# RAM_64K.net
KiCad netlist of a schematic drawn in EAGLE
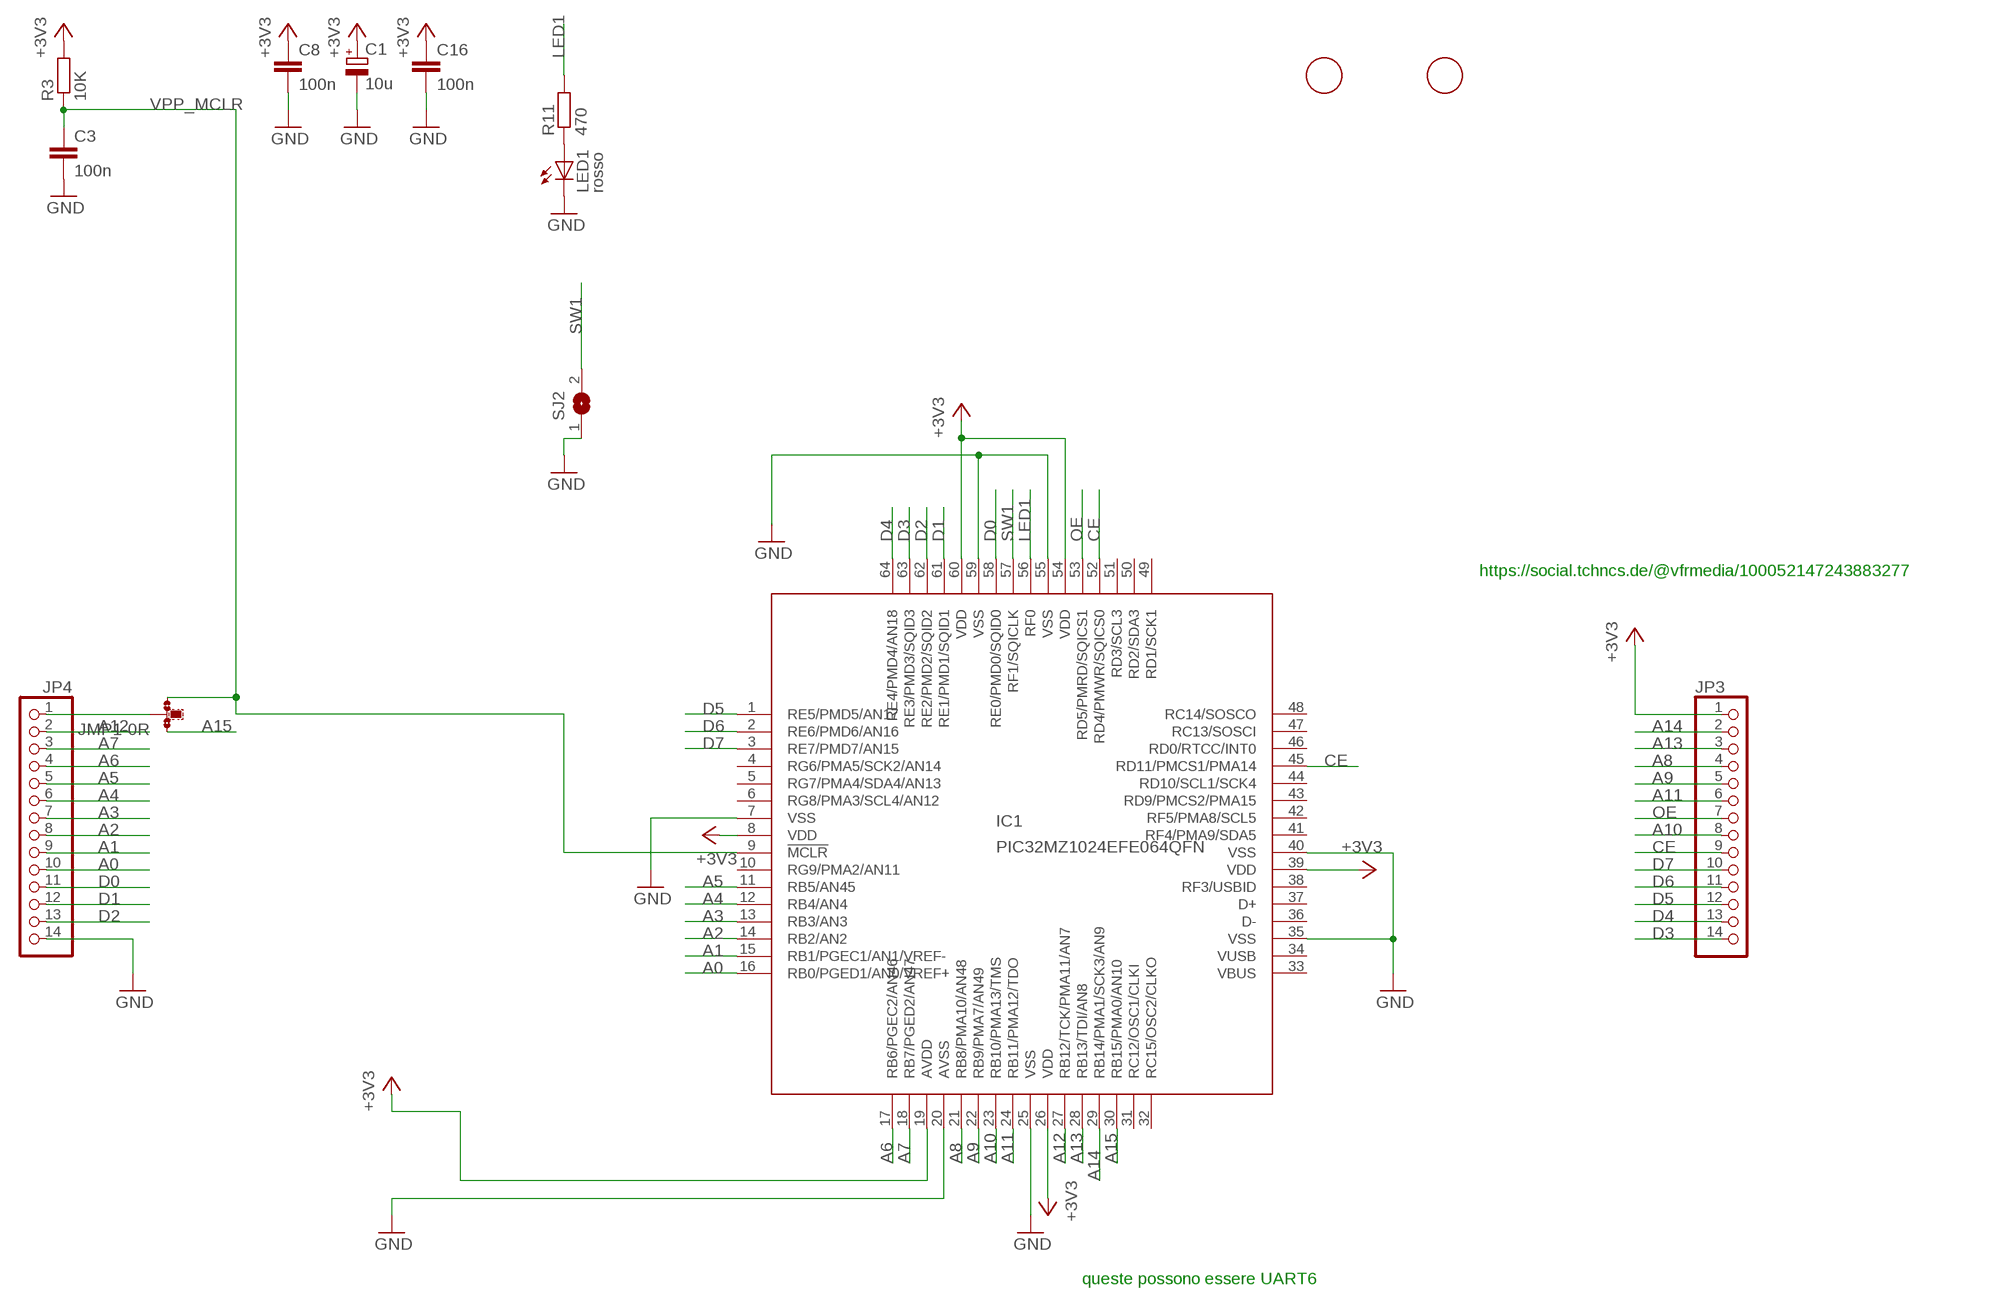
[diagram p0: schematic, sheet 1]

(export (version "E")
  (design (tool "Eeschema 10.0.6"))
  (components
    (comp (ref "C1")
      (value "10u")
      (footprint "eagle-import:SMC_B")
      (libsource (lib "eagle-import") (part "CPOL-EUSMCB"))
    )
    (comp (ref "C3")
      (value "100n")
      (footprint "eagle-import:C0805")
      (libsource (lib "eagle-import") (part "C-EUC0805"))
    )
    (comp (ref "C8")
      (value "100n")
      (footprint "eagle-import:C0805")
      (libsource (lib "eagle-import") (part "C-EUC0805"))
    )
    (comp (ref "C16")
      (value "100n")
      (footprint "eagle-import:C0805")
      (libsource (lib "eagle-import") (part "C-EUC0805"))
    )
    (comp (ref "F1")
      (value "FIDUCIAL")
      (footprint "eagle-import:FIDUCIAL_1MM")
      (libsource (lib "eagle-import") (part "FIDUCIAL"))
    )
    (comp (ref "F2")
      (value "FIDUCIAL")
      (footprint "eagle-import:FIDUCIAL_1MM")
      (libsource (lib "eagle-import") (part "FIDUCIAL"))
    )
    (comp (ref "IC1")
      (value "PIC32MZ1024EFE064QFN")
      (footprint "eagle-import:QFN64")
      (libsource (lib "eagle-import") (part "PIC32MZ1024EFE064QFN"))
    )
    (comp (ref "JMP1")
      (value "0R-JUMPC")
      (footprint "eagle-import:C0R-JMP")
      (libsource (lib "eagle-import") (part "0R-JUMPC"))
    )
    (comp (ref "JP3")
      (value "PINHD-1X14_2.54")
      (footprint "eagle-import:1X14")
      (libsource (lib "eagle-import") (part "PINHD-1X14_2.54"))
    )
    (comp (ref "JP4")
      (value "PINHD-1X14_2.54")
      (footprint "eagle-import:1X14")
      (libsource (lib "eagle-import") (part "PINHD-1X14_2.54"))
    )
    (comp (ref "LED1")
      (value "rosso")
      (footprint "eagle-import:CHIPLED_0805")
      (libsource (lib "eagle-import") (part "LEDCHIPLED_0805"))
    )
    (comp (ref "R3")
      (value "10K")
      (footprint "eagle-import:R0805")
      (libsource (lib "eagle-import") (part "R-EU_R0805"))
    )
    (comp (ref "R11")
      (value "470")
      (footprint "eagle-import:R0805")
      (libsource (lib "eagle-import") (part "R-EU_R0805"))
    )
    (comp (ref "SJ2") (value "SJ") (footprint "eagle-import:SJ") (libsource (lib "eagle-import") (part "SJ")))
  )
  (nets
    (net (code "1") (name "+3V3") (class "Default")
      (node (ref "C1") (pin "+") (pinfunction "+_+") (pintype "passive"))
      (node (ref "C16") (pin "1") (pinfunction "1_1") (pintype "passive"))
      (node (ref "C8") (pin "1") (pinfunction "1_1") (pintype "passive"))
      (node (ref "IC1") (pin "19") (pinfunction "AVDD_19") (pintype "power_in"))
      (node (ref "IC1") (pin "26") (pinfunction "VDD_26") (pintype "power_in"))
      (node (ref "IC1") (pin "39") (pinfunction "VDD_39") (pintype "power_in"))
      (node (ref "IC1") (pin "54") (pinfunction "VDD_54") (pintype "power_in"))
      (node (ref "IC1") (pin "60") (pinfunction "VDD_60") (pintype "power_in"))
      (node (ref "IC1") (pin "8") (pinfunction "VDD_8") (pintype "power_in"))
      (node (ref "JP3") (pin "1") (pinfunction "1_1") (pintype "passive"))
      (node (ref "R3") (pin "2") (pinfunction "2_2") (pintype "passive"))
    )
    (net (code "2") (name "/A0") (class "Default")
      (node (ref "IC1") (pin "16") (pinfunction "RB0/PGED1/AN0/VREF+_16") (pintype "bidirectional"))
      (node (ref "JP4") (pin "10") (pinfunction "10_10") (pintype "passive"))
    )
    (net (code "3") (name "/A1") (class "Default")
      (node (ref "IC1") (pin "15") (pinfunction "RB1/PGEC1/AN1/VREF-_15") (pintype "bidirectional"))
      (node (ref "JP4") (pin "9") (pinfunction "9_9") (pintype "passive"))
    )
    (net (code "4") (name "/A2") (class "Default")
      (node (ref "IC1") (pin "14") (pinfunction "RB2/AN2_14") (pintype "bidirectional"))
      (node (ref "JP4") (pin "8") (pinfunction "8_8") (pintype "passive"))
    )
    (net (code "5") (name "/A3") (class "Default")
      (node (ref "IC1") (pin "13") (pinfunction "RB3/AN3_13") (pintype "bidirectional"))
      (node (ref "JP4") (pin "7") (pinfunction "7_7") (pintype "passive"))
    )
    (net (code "6") (name "/A4") (class "Default")
      (node (ref "IC1") (pin "12") (pinfunction "RB4/AN4_12") (pintype "bidirectional"))
      (node (ref "JP4") (pin "6") (pinfunction "6_6") (pintype "passive"))
    )
    (net (code "7") (name "/A5") (class "Default")
      (node (ref "IC1") (pin "11") (pinfunction "RB5/AN45_11") (pintype "bidirectional"))
      (node (ref "JP4") (pin "5") (pinfunction "5_5") (pintype "passive"))
    )
    (net (code "8") (name "/A6") (class "Default")
      (node (ref "IC1") (pin "17") (pinfunction "RB6/PGEC2/AN46_17") (pintype "bidirectional"))
      (node (ref "JP4") (pin "4") (pinfunction "4_4") (pintype "passive"))
    )
    (net (code "9") (name "/A7") (class "Default")
      (node (ref "IC1") (pin "18") (pinfunction "RB7/PGED2/AN47_18") (pintype "bidirectional"))
      (node (ref "JP4") (pin "3") (pinfunction "3_3") (pintype "passive"))
    )
    (net (code "10") (name "/A8") (class "Default")
      (node (ref "IC1") (pin "21") (pinfunction "RB8/PMA10/AN48_21") (pintype "bidirectional"))
      (node (ref "JP3") (pin "4") (pinfunction "4_4") (pintype "passive"))
    )
    (net (code "11") (name "/A9") (class "Default")
      (node (ref "IC1") (pin "22") (pinfunction "RB9/PMA7/AN49_22") (pintype "bidirectional"))
      (node (ref "JP3") (pin "5") (pinfunction "5_5") (pintype "passive"))
    )
    (net (code "12") (name "/A10") (class "Default")
      (node (ref "IC1") (pin "23") (pinfunction "RB10/PMA13/TMS_23") (pintype "bidirectional"))
      (node (ref "JP3") (pin "8") (pinfunction "8_8") (pintype "passive"))
    )
    (net (code "13") (name "/A11") (class "Default")
      (node (ref "IC1") (pin "24") (pinfunction "RB11/PMA12/TDO_24") (pintype "bidirectional"))
      (node (ref "JP3") (pin "6") (pinfunction "6_6") (pintype "passive"))
    )
    (net (code "14") (name "/A12") (class "Default")
      (node (ref "IC1") (pin "27") (pinfunction "RB12/TCK/PMA11/AN7_27") (pintype "bidirectional"))
      (node (ref "JP4") (pin "2") (pinfunction "2_2") (pintype "passive"))
    )
    (net (code "15") (name "/A13") (class "Default")
      (node (ref "IC1") (pin "28") (pinfunction "RB13/TDI/AN8_28") (pintype "bidirectional"))
      (node (ref "JP3") (pin "3") (pinfunction "3_3") (pintype "passive"))
    )
    (net (code "16") (name "/A14") (class "Default")
      (node (ref "IC1") (pin "29") (pinfunction "RB14/PMA1/SCK3/AN9_29") (pintype "bidirectional"))
      (node (ref "JP3") (pin "2") (pinfunction "2_2") (pintype "passive"))
    )
    (net (code "17") (name "/A15") (class "Default")
      (node (ref "IC1") (pin "30") (pinfunction "RB15/PMA0/AN10_30") (pintype "bidirectional"))
      (node (ref "JMP1") (pin "1") (pinfunction "1_1") (pintype "passive"))
    )
    (net (code "18") (name "/CE") (class "Default")
      (node (ref "IC1") (pin "45") (pinfunction "RD11/PMCS1/PMA14_45") (pintype "bidirectional"))
      (node (ref "IC1") (pin "52") (pinfunction "RD4/PMWR/SQICS0_52") (pintype "bidirectional"))
      (node (ref "JP3") (pin "9") (pinfunction "9_9") (pintype "passive"))
    )
    (net (code "19") (name "/D0") (class "Default")
      (node (ref "IC1") (pin "58") (pinfunction "RE0/PMD0/SQID0_58") (pintype "bidirectional"))
      (node (ref "JP4") (pin "11") (pinfunction "11_11") (pintype "passive"))
    )
    (net (code "20") (name "/D1") (class "Default")
      (node (ref "IC1") (pin "61") (pinfunction "RE1/PMD1/SQID1_61") (pintype "bidirectional"))
      (node (ref "JP4") (pin "12") (pinfunction "12_12") (pintype "passive"))
    )
    (net (code "21") (name "/D2") (class "Default")
      (node (ref "IC1") (pin "62") (pinfunction "RE2/PMD2/SQID2_62") (pintype "bidirectional"))
      (node (ref "JP4") (pin "13") (pinfunction "13_13") (pintype "passive"))
    )
    (net (code "22") (name "/D3") (class "Default")
      (node (ref "IC1") (pin "63") (pinfunction "RE3/PMD3/SQID3_63") (pintype "bidirectional"))
      (node (ref "JP3") (pin "14") (pinfunction "14_14") (pintype "passive"))
    )
    (net (code "23") (name "/D4") (class "Default")
      (node (ref "IC1") (pin "64") (pinfunction "RE4/PMD4/AN18_64") (pintype "bidirectional"))
      (node (ref "JP3") (pin "13") (pinfunction "13_13") (pintype "passive"))
    )
    (net (code "24") (name "/D5") (class "Default")
      (node (ref "IC1") (pin "1") (pinfunction "RE5/PMD5/AN17_1") (pintype "bidirectional"))
      (node (ref "JP3") (pin "12") (pinfunction "12_12") (pintype "passive"))
    )
    (net (code "25") (name "/D6") (class "Default")
      (node (ref "IC1") (pin "2") (pinfunction "RE6/PMD6/AN16_2") (pintype "bidirectional"))
      (node (ref "JP3") (pin "11") (pinfunction "11_11") (pintype "passive"))
    )
    (net (code "26") (name "/D7") (class "Default")
      (node (ref "IC1") (pin "3") (pinfunction "RE7/PMD7/AN15_3") (pintype "bidirectional"))
      (node (ref "JP3") (pin "10") (pinfunction "10_10") (pintype "passive"))
    )
    (net (code "27") (name "/LED1") (class "Default")
      (node (ref "IC1") (pin "56") (pinfunction "RF0_56") (pintype "bidirectional"))
      (node (ref "R11") (pin "2") (pinfunction "2_2") (pintype "passive"))
    )
    (net (code "28") (name "/OE") (class "Default")
      (node (ref "IC1") (pin "53") (pinfunction "RD5/PMRD/SQICS1_53") (pintype "bidirectional"))
      (node (ref "JP3") (pin "7") (pinfunction "7_7") (pintype "passive"))
    )
    (net (code "29") (name "/SW1") (class "Default")
      (node (ref "IC1") (pin "57") (pinfunction "RF1/SQICLK_57") (pintype "bidirectional"))
      (node (ref "SJ2") (pin "2") (pinfunction "2_2") (pintype "passive"))
    )
    (net (code "30") (name "/VPP_MCLR") (class "Default")
      (node (ref "C3") (pin "1") (pinfunction "1_1") (pintype "passive"))
      (node (ref "IC1") (pin "9") (pinfunction "~{MCLR}_9") (pintype "input"))
      (node (ref "JMP1") (pin "3") (pinfunction "3_3") (pintype "passive"))
      (node (ref "R3") (pin "1") (pinfunction "1_1") (pintype "passive"))
    )
    (net (code "31") (name "/VUSB") (class "Default")
      (node (ref "IC1") (pin "34") (pinfunction "VUSB_34") (pintype "power_in"))
    )
    (net (code "32") (name "GND") (class "Default")
      (node (ref "C1") (pin "-") (pinfunction "-_-") (pintype "passive"))
      (node (ref "C16") (pin "2") (pinfunction "2_2") (pintype "passive"))
      (node (ref "C3") (pin "2") (pinfunction "2_2") (pintype "passive"))
      (node (ref "C8") (pin "2") (pinfunction "2_2") (pintype "passive"))
      (node (ref "IC1") (pin "20") (pinfunction "AVSS_20") (pintype "power_in"))
      (node (ref "IC1") (pin "25") (pinfunction "VSS_25") (pintype "power_in"))
      (node (ref "IC1") (pin "35") (pinfunction "VSS_35") (pintype "power_in"))
      (node (ref "IC1") (pin "40") (pinfunction "VSS_40") (pintype "power_in"))
      (node (ref "IC1") (pin "55") (pinfunction "VSS_55") (pintype "power_in"))
      (node (ref "IC1") (pin "59") (pinfunction "VSS_59") (pintype "power_in"))
      (node (ref "IC1") (pin "7") (pinfunction "VSS_7") (pintype "power_in"))
      (node (ref "JP4") (pin "14") (pinfunction "14_14") (pintype "passive"))
      (node (ref "LED1") (pin "C") (pinfunction "C_C") (pintype "passive"))
      (node (ref "SJ2") (pin "1") (pinfunction "1_1") (pintype "passive"))
    )
    (net (code "33") (name "Net-(JMP1-Pad2)") (class "Default")
      (node (ref "JMP1") (pin "2") (pinfunction "2_2") (pintype "passive"))
      (node (ref "JP4") (pin "1") (pinfunction "1_1") (pintype "passive"))
    )
    (net (code "34") (name "Net-(LED1-PadA)") (class "Default")
      (node (ref "LED1") (pin "A") (pinfunction "A_A") (pintype "passive"))
      (node (ref "R11") (pin "1") (pinfunction "1_1") (pintype "passive"))
    )
    (net (code "35") (name "unconnected-(IC1-D+-Pad37)") (class "Default")
      (node (ref "IC1") (pin "37") (pinfunction "D+_37") (pintype "passive"))
    )
    (net (code "36") (name "unconnected-(IC1-D--Pad36)") (class "Default")
      (node (ref "IC1") (pin "36") (pinfunction "D-_36") (pintype "passive"))
    )
    (net (code "37") (name "unconnected-(IC1-RC12{slash}OSC1{slash}CLKI-Pad31)") (class "Default")
      (node (ref "IC1") (pin "31") (pinfunction "RC12/OSC1/CLKI_31") (pintype "bidirectional"))
    )
    (net (code "38") (name "unconnected-(IC1-RC13{slash}SOSCI-Pad47)") (class "Default")
      (node (ref "IC1") (pin "47") (pinfunction "RC13/SOSCI_47") (pintype "bidirectional"))
    )
    (net (code "39") (name "unconnected-(IC1-RC14{slash}SOSCO-Pad48)") (class "Default")
      (node (ref "IC1") (pin "48") (pinfunction "RC14/SOSCO_48") (pintype "bidirectional"))
    )
    (net (code "40") (name "unconnected-(IC1-RC15{slash}OSC2{slash}CLKO-Pad32)") (class "Default")
      (node (ref "IC1") (pin "32") (pinfunction "RC15/OSC2/CLKO_32") (pintype "bidirectional"))
    )
    (net (code "41") (name "unconnected-(IC1-RD0{slash}RTCC{slash}INT0-Pad46)") (class "Default")
      (node (ref "IC1") (pin "46") (pinfunction "RD0/RTCC/INT0_46") (pintype "bidirectional"))
    )
    (net (code "42") (name "unconnected-(IC1-RD1{slash}SCK1-Pad49)") (class "Default")
      (node (ref "IC1") (pin "49") (pinfunction "RD1/SCK1_49") (pintype "bidirectional"))
    )
    (net (code "43") (name "unconnected-(IC1-RD2{slash}SDA3-Pad50)") (class "Default")
      (node (ref "IC1") (pin "50") (pinfunction "RD2/SDA3_50") (pintype "bidirectional"))
    )
    (net (code "44") (name "unconnected-(IC1-RD3{slash}SCL3-Pad51)") (class "Default")
      (node (ref "IC1") (pin "51") (pinfunction "RD3/SCL3_51") (pintype "bidirectional"))
    )
    (net (code "45") (name "unconnected-(IC1-RD9{slash}PMCS2{slash}PMA15-Pad43)") (class "Default")
      (node (ref "IC1") (pin "43") (pinfunction "RD9/PMCS2/PMA15_43") (pintype "bidirectional"))
    )
    (net (code "46") (name "unconnected-(IC1-RD10{slash}SCL1{slash}SCK4-Pad44)") (class "Default")
      (node (ref "IC1") (pin "44") (pinfunction "RD10/SCL1/SCK4_44") (pintype "bidirectional"))
    )
    (net (code "47") (name "unconnected-(IC1-RF3{slash}USBID-Pad38)") (class "Default")
      (node (ref "IC1") (pin "38") (pinfunction "RF3/USBID_38") (pintype "bidirectional"))
    )
    (net (code "48") (name "unconnected-(IC1-RF4{slash}PMA9{slash}SDA5-Pad41)") (class "Default")
      (node (ref "IC1") (pin "41") (pinfunction "RF4/PMA9/SDA5_41") (pintype "bidirectional"))
    )
    (net (code "49") (name "unconnected-(IC1-RF5{slash}PMA8{slash}SCL5-Pad42)") (class "Default")
      (node (ref "IC1") (pin "42") (pinfunction "RF5/PMA8/SCL5_42") (pintype "bidirectional"))
    )
    (net (code "50") (name "unconnected-(IC1-RG6{slash}PMA5{slash}SCK2{slash}AN14-Pad4)") (class "Default")
      (node (ref "IC1") (pin "4") (pinfunction "RG6/PMA5/SCK2/AN14_4") (pintype "bidirectional"))
    )
    (net (code "51") (name "unconnected-(IC1-RG7{slash}PMA4{slash}SDA4{slash}AN13-Pad5)") (class "Default")
      (node (ref "IC1") (pin "5") (pinfunction "RG7/PMA4/SDA4/AN13_5") (pintype "bidirectional"))
    )
    (net (code "52") (name "unconnected-(IC1-RG8{slash}PMA3{slash}SCL4{slash}AN12-Pad6)") (class "Default")
      (node (ref "IC1") (pin "6") (pinfunction "RG8/PMA3/SCL4/AN12_6") (pintype "bidirectional"))
    )
    (net (code "53") (name "unconnected-(IC1-RG9{slash}PMA2{slash}AN11-Pad10)") (class "Default")
      (node (ref "IC1") (pin "10") (pinfunction "RG9/PMA2/AN11_10") (pintype "bidirectional"))
    )
    (net (code "54") (name "unconnected-(IC1-VBUS-Pad33)") (class "Default")
      (node (ref "IC1") (pin "33") (pinfunction "VBUS_33") (pintype "passive"))
    )
  )
)
